# GlassHeat.net
KiCad netlist of a schematic drawn in EAGLE
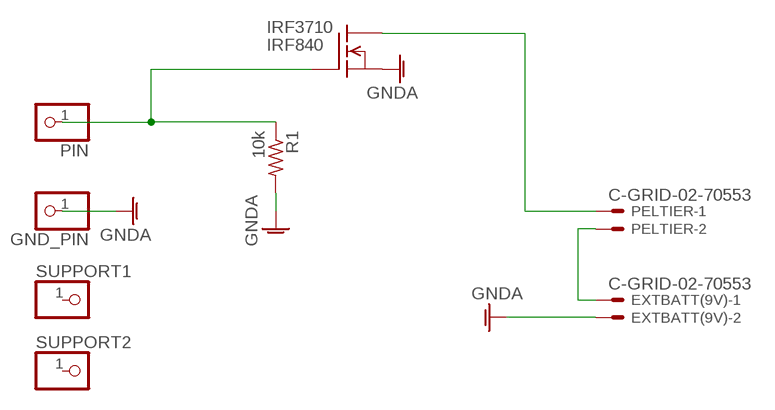
[diagram p0: schematic, sheet 1]

(export (version "E")
  (design (tool "Eeschema 10.0.6"))
  (components
    (comp (ref "EXTBATT(9V)")
      (value "C-GRID-02-70553")
      (footprint "eagle-import:70553-02")
      (libsource (lib "eagle-import") (part "C-GRID-02-70553"))
    )
    (comp (ref "GND_PIN")
      (value "PINHD-1X1")
      (footprint "eagle-import:1X01")
      (libsource (lib "eagle-import") (part "PINHD-1X1"))
    )
    (comp (ref "IRF3710")
      (value "IRF840")
      (footprint "eagle-import:TO220")
      (libsource (lib "eagle-import") (part "IRF840"))
    )
    (comp (ref "PELTIER")
      (value "C-GRID-02-70553")
      (footprint "eagle-import:70553-02")
      (libsource (lib "eagle-import") (part "C-GRID-02-70553"))
    )
    (comp (ref "PIN")
      (value "PINHD-1X1")
      (footprint "eagle-import:1X01")
      (libsource (lib "eagle-import") (part "PINHD-1X1"))
    )
    (comp (ref "R1")
      (value "10k")
      (footprint "eagle-import:0207_7")
      (libsource (lib "eagle-import") (part "R-US_0207/7"))
    )
    (comp (ref "SUPPORT1")
      (value "PINHD-1X1")
      (footprint "eagle-import:1X01")
      (libsource (lib "eagle-import") (part "PINHD-1X1"))
    )
    (comp (ref "SUPPORT2")
      (value "PINHD-1X1")
      (footprint "eagle-import:1X01")
      (libsource (lib "eagle-import") (part "PINHD-1X1"))
    )
  )
  (nets
    (net (code "1") (name "GNDA") (class "Default")
      (node (ref "EXTBATT(9V)") (pin "2") (pinfunction "S_2") (pintype "passive"))
      (node (ref "GND_PIN") (pin "1") (pinfunction "1_1") (pintype "passive"))
      (node (ref "IRF3710") (pin "3") (pinfunction "S_3") (pintype "passive"))
      (node (ref "R1") (pin "2") (pinfunction "2_2") (pintype "passive"))
    )
    (net (code "2") (name "Net-(EXTBATT(9V)A-S)") (class "Default")
      (node (ref "EXTBATT(9V)") (pin "1") (pinfunction "S_1") (pintype "passive"))
      (node (ref "PELTIER") (pin "2") (pinfunction "S_2") (pintype "passive"))
    )
    (net (code "3") (name "Net-(IRF3710-D)") (class "Default")
      (node (ref "IRF3710") (pin "2") (pinfunction "D_2") (pintype "passive"))
      (node (ref "PELTIER") (pin "1") (pinfunction "S_1") (pintype "passive"))
    )
    (net (code "4") (name "Net-(IRF3710-G)") (class "Default")
      (node (ref "IRF3710") (pin "1") (pinfunction "G_1") (pintype "passive"))
      (node (ref "PIN") (pin "1") (pinfunction "1_1") (pintype "passive"))
      (node (ref "R1") (pin "1") (pinfunction "1_1") (pintype "passive"))
    )
    (net (code "5") (name "unconnected-(SUPPORT1-Pad1)") (class "Default")
      (node (ref "SUPPORT1") (pin "1") (pinfunction "1_1") (pintype "passive"))
    )
    (net (code "6") (name "unconnected-(SUPPORT2-Pad1)") (class "Default")
      (node (ref "SUPPORT2") (pin "1") (pinfunction "1_1") (pintype "passive"))
    )
  )
)
